# sch.net
KiCad netlist of a schematic drawn in Altium Designer
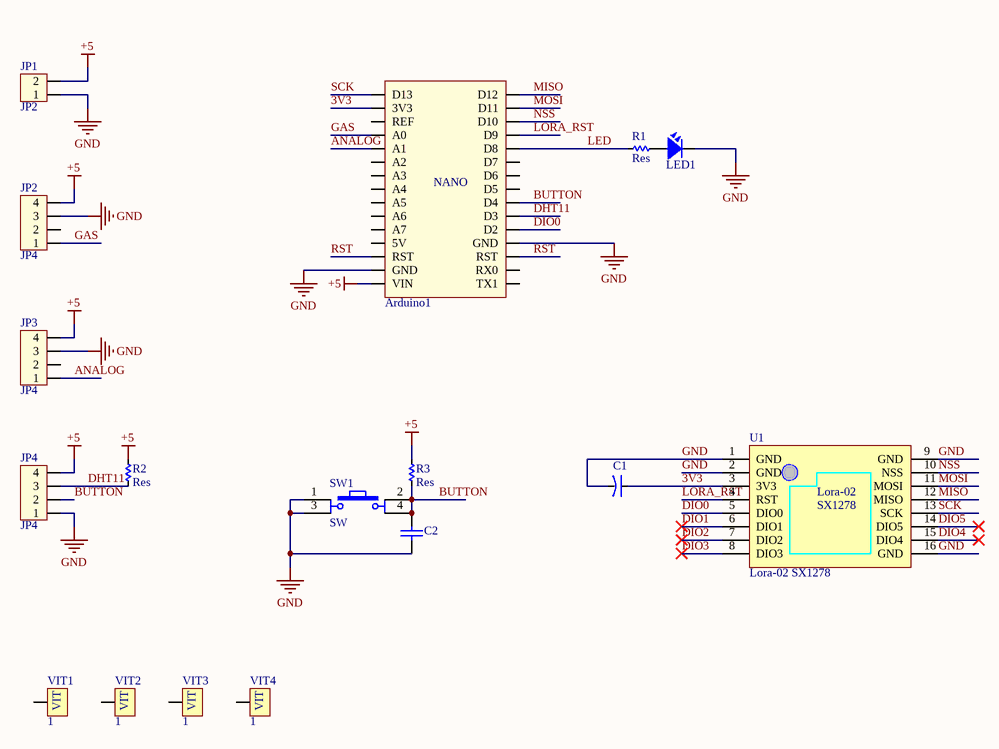
[diagram p0: sch.SchDoc]

(export (version "E")
  (design (tool "Eeschema 10.0.6"))
  (components
    (comp (ref "Arduino1")
      (value "Arduino Nano")
      (footprint "Arduino Nano")
      (description "Arduino NANO")
      (libsource (lib "Thư Viện Altium FULL HD") (part "Arduino Nano"))
    )
    (comp (ref "C1")
      (value "CN-ALU-DIP")
      (footprint "CA-ALU-5W")
      (description "Capacitor (Semiconductor SIM Model)")
      (fields (field (name "PUBLISHER") "Altium Limited"))
      (libsource (lib "Thư Viện Altium FULL HD") (part "CN-ALU-DIP"))
    )
    (comp (ref "C2")
      (value "Capacitor Ceramic")
      (footprint "C0805")
      (description "Capacitor")
      (fields (field (name "PUBLISHER") "Altium Limited"))
      (libsource (lib "My Library") (part "CapSMD"))
    )
    (comp (ref "JP1")
      (value "JP2")
      (footprint "CON2")
      (description "Connector 2")
      (libsource (lib "My Library") (part "Con2"))
    )
    (comp (ref "JP2")
      (value "JP4")
      (footprint "CON4")
      (description "Connector 4")
      (libsource (lib "My Library") (part "Con4"))
    )
    (comp (ref "JP3")
      (value "JP4")
      (footprint "CON4")
      (description "Connector 4")
      (libsource (lib "My Library") (part "Con4"))
    )
    (comp (ref "JP4")
      (value "JP4")
      (footprint "CON4")
      (description "Connector 4")
      (libsource (lib "My Library") (part "Con4"))
    )
    (comp (ref "LED1")
      (value "LED")
      (footprint "LED-3MM-YELLOW")
      (description "LED Single colour Green and Red")
      (libsource (lib "Thư Viện Altium FULL HD") (part "LED"))
    )
    (comp (ref "R1")
      (value "Res")
      (footprint "RES-SMD-1206")
      (description "Resistor")
      (fields
        (field (name "MANUFACTURER") "Generic Components")
        (field (name "PUBLISHER") "Altium Hobart Technology Centre")
      )
      (libsource (lib "Thư Viện Altium FULL HD") (part "Res-SMD"))
    )
    (comp (ref "R2")
      (value "Res")
      (footprint "RES-SMD-1206")
      (description "Resistor")
      (fields
        (field (name "MANUFACTURER") "Generic Components")
        (field (name "PUBLISHER") "Altium Hobart Technology Centre")
      )
      (libsource (lib "Thư Viện Altium FULL HD") (part "Res-SMD"))
    )
    (comp (ref "R3")
      (value "Res")
      (footprint "RES-SMD-1206")
      (description "Resistor")
      (fields
        (field (name "MANUFACTURER") "Generic Components")
        (field (name "PUBLISHER") "Altium Hobart Technology Centre")
      )
      (libsource (lib "Thư Viện Altium FULL HD") (part "Res-SMD"))
    )
    (comp (ref "SW1")
      (value "SW")
      (footprint "SW4")
      (description "Switch button 4 pin")
      (libsource (lib "My Library") (part "SW4"))
    )
    (comp (ref "U1")
      (value "Lora-02 SX1278")
      (footprint "Lora02-sx1278")
      (description "Lora-02 sx1278")
      (libsource (lib "Lora02-sx1278") (part "Lora-02 SX1278"))
    )
    (comp (ref "VIT1")
      (value "1")
      (footprint "VIT")
      (description "Oc Vit")
      (libsource (lib "My Library") (part "VIT"))
    )
    (comp (ref "VIT2")
      (value "1")
      (footprint "VIT")
      (description "Oc Vit")
      (libsource (lib "My Library") (part "VIT"))
    )
    (comp (ref "VIT3")
      (value "1")
      (footprint "VIT")
      (description "Oc Vit")
      (libsource (lib "My Library") (part "VIT"))
    )
    (comp (ref "VIT4")
      (value "1")
      (footprint "VIT")
      (description "Oc Vit")
      (libsource (lib "My Library") (part "VIT"))
    )
  )
  (nets
    (net (code "1") (name "+5") (class "Default")
      (node (ref "Arduino1") (pin "VIN") (pinfunction "VIN_VIN") (pintype "passive"))
      (node (ref "JP1") (pin "2") (pinfunction "2_2") (pintype "passive"))
      (node (ref "JP2") (pin "4") (pinfunction "4_4") (pintype "passive"))
      (node (ref "JP3") (pin "4") (pinfunction "4_4") (pintype "passive"))
      (node (ref "JP4") (pin "4") (pinfunction "4_4") (pintype "passive"))
      (node (ref "R2") (pin "2") (pinfunction "2_2") (pintype "passive"))
      (node (ref "R3") (pin "1") (pinfunction "1_1") (pintype "passive"))
    )
    (net (code "2") (name "/3V3") (class "Default")
      (node (ref "Arduino1") (pin "3V3") (pinfunction "3V3_3V3") (pintype "passive"))
      (node (ref "C1") (pin "1") (pinfunction "1_1") (pintype "passive"))
      (node (ref "U1") (pin "3") (pinfunction "3V3_3") (pintype "passive"))
    )
    (net (code "3") (name "/ANALOG") (class "Default")
      (node (ref "Arduino1") (pin "A1") (pinfunction "A1_A1") (pintype "passive"))
      (node (ref "JP3") (pin "1") (pinfunction "1_1") (pintype "passive"))
    )
    (net (code "4") (name "/BUTTON") (class "Default")
      (node (ref "Arduino1") (pin "D4") (pinfunction "D4_D4") (pintype "passive"))
      (node (ref "C2") (pin "2") (pinfunction "2_2") (pintype "passive"))
      (node (ref "JP4") (pin "2") (pinfunction "2_2") (pintype "passive"))
      (node (ref "R3") (pin "2") (pinfunction "2_2") (pintype "passive"))
      (node (ref "SW1") (pin "2") (pintype "passive"))
      (node (ref "SW1") (pin "4") (pintype "passive"))
    )
    (net (code "5") (name "/DHT11") (class "Default")
      (node (ref "Arduino1") (pin "D3") (pinfunction "D3_D3") (pintype "passive"))
      (node (ref "JP4") (pin "3") (pinfunction "3_3") (pintype "passive"))
      (node (ref "R2") (pin "1") (pinfunction "1_1") (pintype "passive"))
    )
    (net (code "6") (name "/DIO0") (class "Default")
      (node (ref "Arduino1") (pin "D2") (pinfunction "D2_D2") (pintype "passive"))
      (node (ref "U1") (pin "5") (pinfunction "DIO0_5") (pintype "passive"))
    )
    (net (code "7") (name "/DIO1") (class "Default")
      (node (ref "U1") (pin "6") (pinfunction "DIO1_6") (pintype "passive+no_connect"))
    )
    (net (code "8") (name "/DIO2") (class "Default")
      (node (ref "U1") (pin "7") (pinfunction "DIO2_7") (pintype "passive+no_connect"))
    )
    (net (code "9") (name "/DIO3") (class "Default")
      (node (ref "U1") (pin "8") (pinfunction "DIO3_8") (pintype "passive+no_connect"))
    )
    (net (code "10") (name "/DIO4") (class "Default")
      (node (ref "U1") (pin "15") (pinfunction "DIO4_15") (pintype "passive+no_connect"))
    )
    (net (code "11") (name "/DIO5") (class "Default")
      (node (ref "U1") (pin "14") (pinfunction "DIO5_14") (pintype "passive+no_connect"))
    )
    (net (code "12") (name "/GAS") (class "Default")
      (node (ref "Arduino1") (pin "A0") (pinfunction "A0_A0") (pintype "passive"))
      (node (ref "JP2") (pin "1") (pinfunction "1_1") (pintype "passive"))
    )
    (net (code "13") (name "/LED") (class "Default")
      (node (ref "Arduino1") (pin "D8") (pinfunction "D8_D8") (pintype "passive"))
      (node (ref "R1") (pin "1") (pinfunction "1_1") (pintype "passive"))
    )
    (net (code "14") (name "/LORA_RST") (class "Default")
      (node (ref "Arduino1") (pin "D9") (pinfunction "D9_D9") (pintype "passive"))
      (node (ref "U1") (pin "4") (pinfunction "RST_4") (pintype "passive"))
    )
    (net (code "15") (name "/MISO") (class "Default")
      (node (ref "Arduino1") (pin "D12") (pinfunction "D12_D12") (pintype "passive"))
      (node (ref "U1") (pin "12") (pinfunction "MISO_12") (pintype "passive"))
    )
    (net (code "16") (name "/MOSI") (class "Default")
      (node (ref "Arduino1") (pin "D11") (pinfunction "D11_D11") (pintype "passive"))
      (node (ref "U1") (pin "11") (pinfunction "MOSI_11") (pintype "passive"))
    )
    (net (code "17") (name "/NSS") (class "Default")
      (node (ref "Arduino1") (pin "D10") (pinfunction "D10_D10") (pintype "passive"))
      (node (ref "U1") (pin "10") (pinfunction "NSS_10") (pintype "passive"))
    )
    (net (code "18") (name "/RST") (class "Default")
      (node (ref "Arduino1") (pin "RST") (pinfunction "RST_RST") (pintype "passive"))
    )
    (net (code "19") (name "/SCK") (class "Default")
      (node (ref "Arduino1") (pin "D13") (pinfunction "D13_D13") (pintype "passive"))
      (node (ref "U1") (pin "13") (pinfunction "SCK_13") (pintype "passive"))
    )
    (net (code "20") (name "GND") (class "Default")
      (node (ref "Arduino1") (pin "GND") (pinfunction "GND_GND") (pintype "passive"))
      (node (ref "C1") (pin "2") (pinfunction "2_2") (pintype "passive"))
      (node (ref "C2") (pin "1") (pinfunction "1_1") (pintype "passive"))
      (node (ref "JP1") (pin "1") (pinfunction "1_1") (pintype "passive"))
      (node (ref "JP2") (pin "3") (pinfunction "3_3") (pintype "passive"))
      (node (ref "JP3") (pin "3") (pinfunction "3_3") (pintype "passive"))
      (node (ref "JP4") (pin "1") (pinfunction "1_1") (pintype "passive"))
      (node (ref "LED1") (pin "2") (pinfunction "2_2") (pintype "passive"))
      (node (ref "SW1") (pin "1") (pintype "passive"))
      (node (ref "SW1") (pin "3") (pintype "passive"))
      (node (ref "U1") (pin "1") (pinfunction "GND_1") (pintype "passive"))
      (node (ref "U1") (pin "16") (pinfunction "GND_16") (pintype "passive"))
      (node (ref "U1") (pin "2") (pinfunction "GND_2") (pintype "passive"))
      (node (ref "U1") (pin "9") (pinfunction "GND_9") (pintype "passive"))
    )
    (net (code "21") (name "Net-(LED1-Pad1)") (class "Default")
      (node (ref "LED1") (pin "1") (pinfunction "1_1") (pintype "passive"))
      (node (ref "R1") (pin "2") (pinfunction "2_2") (pintype "passive"))
    )
    (net (code "22") (name "unconnected-(Arduino1-Pad5V)") (class "Default")
      (node (ref "Arduino1") (pin "5V") (pinfunction "5V_5V") (pintype "passive"))
    )
    (net (code "23") (name "unconnected-(Arduino1-PadA2)") (class "Default")
      (node (ref "Arduino1") (pin "A2") (pinfunction "A2_A2") (pintype "passive"))
    )
    (net (code "24") (name "unconnected-(Arduino1-PadA3)") (class "Default")
      (node (ref "Arduino1") (pin "A3") (pinfunction "A3_A3") (pintype "passive"))
    )
    (net (code "25") (name "unconnected-(Arduino1-PadA4)") (class "Default")
      (node (ref "Arduino1") (pin "A4") (pinfunction "A4_A4") (pintype "passive"))
    )
    (net (code "26") (name "unconnected-(Arduino1-PadA5)") (class "Default")
      (node (ref "Arduino1") (pin "A5") (pinfunction "A5_A5") (pintype "passive"))
    )
    (net (code "27") (name "unconnected-(Arduino1-PadA6)") (class "Default")
      (node (ref "Arduino1") (pin "A6") (pinfunction "A6_A6") (pintype "passive"))
    )
    (net (code "28") (name "unconnected-(Arduino1-PadA7)") (class "Default")
      (node (ref "Arduino1") (pin "A7") (pinfunction "A7_A7") (pintype "passive"))
    )
    (net (code "29") (name "unconnected-(Arduino1-PadD5)") (class "Default")
      (node (ref "Arduino1") (pin "D5") (pinfunction "D5_D5") (pintype "passive"))
    )
    (net (code "30") (name "unconnected-(Arduino1-PadD6)") (class "Default")
      (node (ref "Arduino1") (pin "D6") (pinfunction "D6_D6") (pintype "passive"))
    )
    (net (code "31") (name "unconnected-(Arduino1-PadD7)") (class "Default")
      (node (ref "Arduino1") (pin "D7") (pinfunction "D7_D7") (pintype "passive"))
    )
    (net (code "32") (name "unconnected-(Arduino1-PadREF)") (class "Default")
      (node (ref "Arduino1") (pin "REF") (pinfunction "REF_REF") (pintype "passive"))
    )
    (net (code "33") (name "unconnected-(Arduino1-PadRX0)") (class "Default")
      (node (ref "Arduino1") (pin "RX0") (pinfunction "RX0_RX0") (pintype "passive"))
    )
    (net (code "34") (name "unconnected-(Arduino1-PadTX1)") (class "Default")
      (node (ref "Arduino1") (pin "TX1") (pinfunction "TX1_TX1") (pintype "passive"))
    )
    (net (code "35") (name "unconnected-(JP2-Pad2)") (class "Default")
      (node (ref "JP2") (pin "2") (pinfunction "2_2") (pintype "passive"))
    )
    (net (code "36") (name "unconnected-(JP3-Pad2)") (class "Default")
      (node (ref "JP3") (pin "2") (pinfunction "2_2") (pintype "passive"))
    )
    (net (code "37") (name "unconnected-(VIT1-1-PadVIT1)") (class "Default")
      (node (ref "VIT1") (pin "VIT1") (pinfunction "1_VIT1") (pintype "passive"))
    )
    (net (code "38") (name "unconnected-(VIT2-1-PadVIT1)") (class "Default")
      (node (ref "VIT2") (pin "VIT1") (pinfunction "1_VIT1") (pintype "passive"))
    )
    (net (code "39") (name "unconnected-(VIT3-1-PadVIT1)") (class "Default")
      (node (ref "VIT3") (pin "VIT1") (pinfunction "1_VIT1") (pintype "passive"))
    )
    (net (code "40") (name "unconnected-(VIT4-1-PadVIT1)") (class "Default")
      (node (ref "VIT4") (pin "VIT1") (pinfunction "1_VIT1") (pintype "passive"))
    )
  )
)
